# EC_Sensor1.net
KiCad netlist of a schematic drawn in Altium Designer
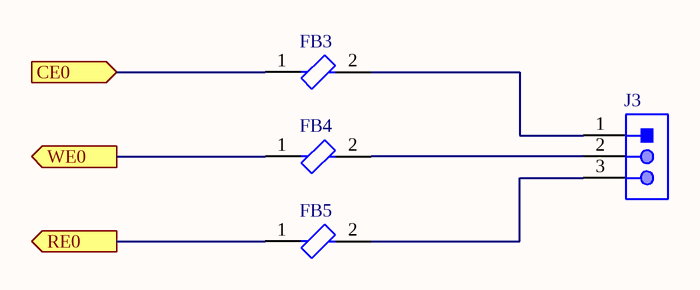
[diagram p0: EC_Sensor1.SchDoc]

(export (version "E")
  (design (tool "Eeschema 10.0.6"))
  (components
    (comp (ref "FB3")
      (value "BLM15PD600SN1D")
      (footprint "FP-BLM15-0_05-d0_7-IPC_B")
      (description "Chip Ferrite Bead, 0402, 60Ω @ 100MHz, 0.06Ω, 25%, 1.7A")
      (fields (field (name "TOLERANCE") "25%"))
      (libsource (lib "Altium Content Vault") (part "5f30dd21d616792df468990f7003faa"))
    )
    (comp (ref "FB4")
      (value "BLM15PD600SN1D")
      (footprint "FP-BLM15-0_05-d0_7-IPC_B")
      (description "Chip Ferrite Bead, 0402, 60Ω @ 100MHz, 0.06Ω, 25%, 1.7A")
      (fields (field (name "TOLERANCE") "25%"))
      (libsource (lib "Altium Content Vault") (part "5f30dd21d616792df468990f7003faa"))
    )
    (comp (ref "FB5")
      (value "BLM15PD600SN1D")
      (footprint "FP-BLM15-0_05-d0_7-IPC_B")
      (description "Chip Ferrite Bead, 0402, 60Ω @ 100MHz, 0.06Ω, 25%, 1.7A")
      (fields (field (name "TOLERANCE") "25%"))
      (libsource (lib "Altium Content Vault") (part "5f30dd21d616792df468990f7003faa"))
    )
    (comp (ref "J3")
      (value "61300311021")
      (footprint "61300311021")
      (description "THT Angled Pin Header WR-PHD, Pitch 2.54 mm, Single Row, 3 pins")
      (fields (field (name "MANUFACTURER") "Wurth Elektronik") (field (name "PUBLISHER") "WurthElektronik"))
      (libsource (lib "Altium Content Vault") (part "WE-CN-1P-M-R3"))
    )
  )
  (nets
    (net (code "1") (name "/CE0") (class "Default")
      (node (ref "FB3") (pin "1") (pinfunction "1_1") (pintype "passive"))
    )
    (net (code "2") (name "/RE0") (class "Default")
      (node (ref "FB5") (pin "1") (pinfunction "1_1") (pintype "passive"))
    )
    (net (code "3") (name "/WE0") (class "Default")
      (node (ref "FB4") (pin "1") (pinfunction "1_1") (pintype "passive"))
    )
    (net (code "4") (name "Net-(FB3-Pad2)") (class "Default")
      (node (ref "FB3") (pin "2") (pinfunction "2_2") (pintype "passive"))
      (node (ref "J3") (pin "1") (pinfunction "1_1") (pintype "passive"))
    )
    (net (code "5") (name "Net-(FB4-Pad2)") (class "Default")
      (node (ref "FB4") (pin "2") (pinfunction "2_2") (pintype "passive"))
      (node (ref "J3") (pin "2") (pinfunction "2_2") (pintype "passive"))
    )
    (net (code "6") (name "Net-(FB5-Pad2)") (class "Default")
      (node (ref "FB5") (pin "2") (pinfunction "2_2") (pintype "passive"))
      (node (ref "J3") (pin "3") (pinfunction "3_3") (pintype "passive"))
    )
  )
)
